# Connectors_U_B.net
KiCad netlist of a schematic drawn in Altium Designer
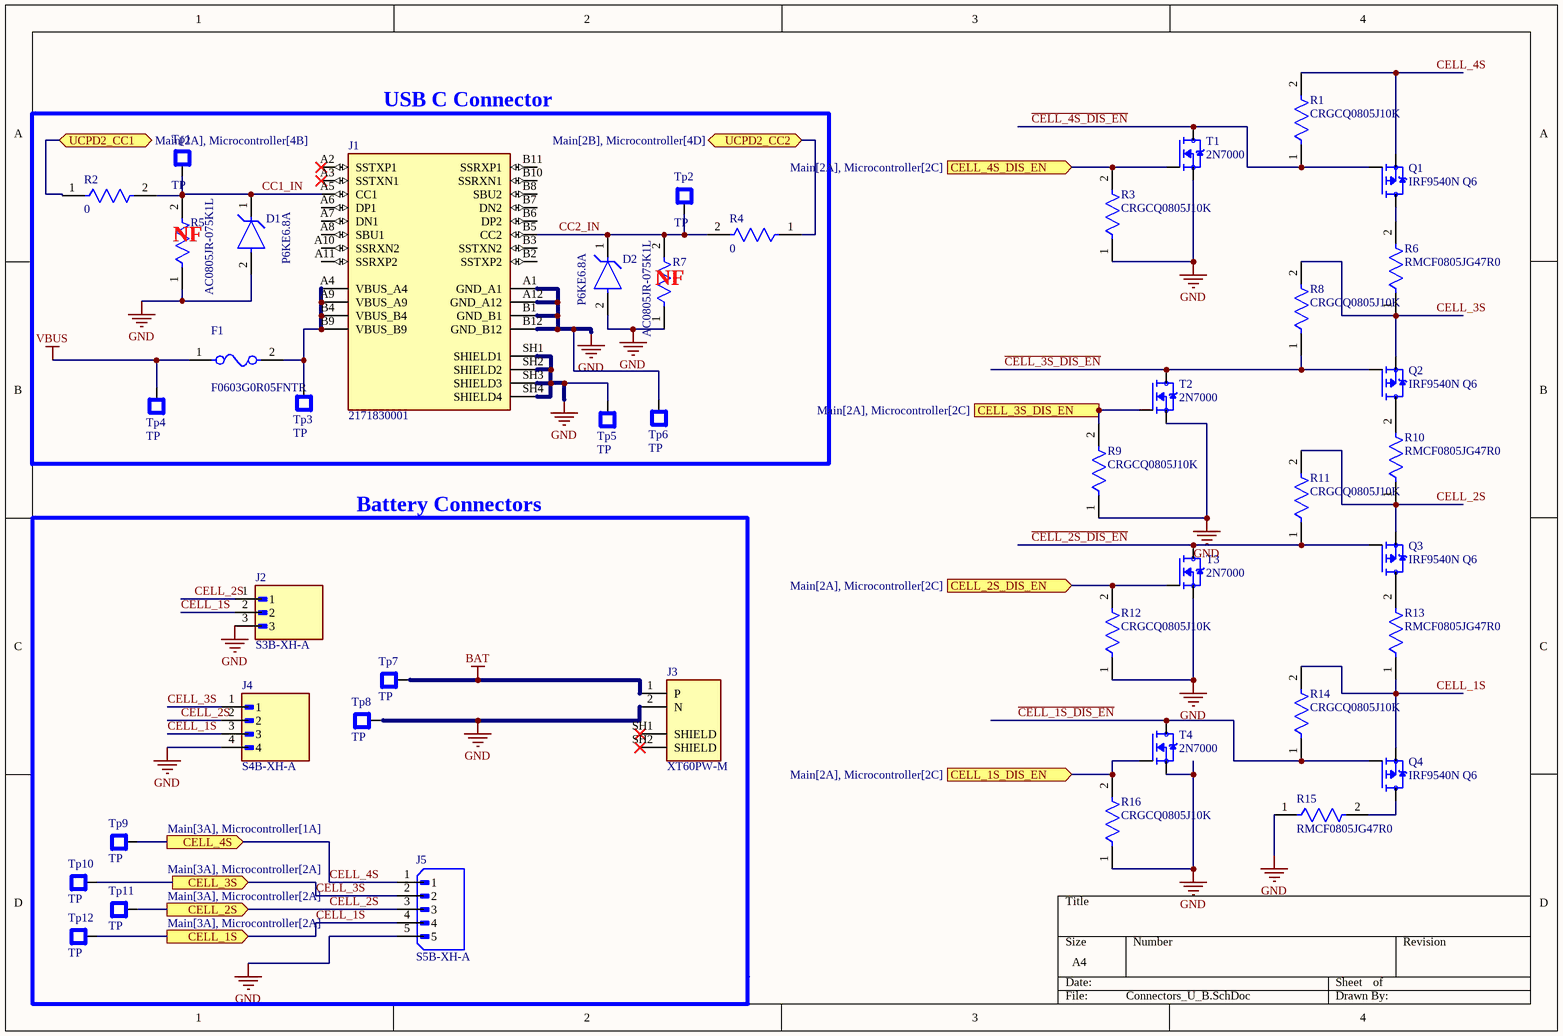
[diagram p0: Connectors_U_B.SchDoc]

(export (version "E")
  (design (tool "Eeschema 10.0.6"))
  (components
    (comp (ref "D1")
      (value "P6KE6.8A")
      (footprint "FP-P6KE-MFG")
      (description "TVS DIODE 5.8V 10.5V DO204AC")
      (fields
        (field (name "MANUFACTURER") "Littelfuse Inc")
        (field (name "OCTOPART") "https://octopart.com/p6ke6.8a-littelfuse-20808")
      )
      (libsource (lib "Altium Content Vault") (part "f813f71cba58e380607f5dd3caf9714"))
    )
    (comp (ref "D2")
      (value "P6KE6.8A")
      (footprint "FP-P6KE-MFG")
      (description "TVS DIODE 5.8V 10.5V DO204AC")
      (fields
        (field (name "MANUFACTURER") "Littelfuse Inc")
        (field (name "OCTOPART") "https://octopart.com/p6ke6.8a-littelfuse-20808")
      )
      (libsource (lib "Altium Content Vault") (part "f813f71cba58e380607f5dd3caf9714"))
    )
    (comp (ref "F1")
      (value "F0603G0R05FNTR")
      (footprint "FP-F0603G-MFG")
      (description "FUSE BOARD MOUNT 50MA 32VDC 0603")
      (fields
        (field (name "OCTOPART") "https://octopart.com/f0603g0r05fntr-avx-21046321")
        (field (name "MANUFACTURER") "AVX Corporation")
      )
      (libsource (lib "Altium Content Vault") (part "5bcf9b9f640e542cf0359d10258e979"))
    )
    (comp (ref "J1")
      (value "2171830001")
      (footprint "MOLEX_2171830001")
      (fields (field (name "MF") "{'manufacturer': u'Molex'}"))
      (libsource (lib "power_schi") (part "2171830001"))
    )
    (comp (ref "J2")
      (value "S3B-XH-A")
      (footprint "JST_S3B-XH-A")
      (libsource (lib "power_schi") (part "S3B-XH-A"))
    )
    (comp (ref "J3")
      (value "XT60PW-M")
      (footprint "AMASS_XT60PW-M")
      (description "Socket, DC supply, male, PIN: 2")
      (fields (field (name "MF") "AMASS"))
      (libsource (lib "power_schi") (part "XT60PW-M"))
    )
    (comp (ref "J4")
      (value "S4B-XH-A")
      (footprint "JST_S4B-XH-A")
      (libsource (lib "power_schi") (part "S4B-XH-A"))
    )
    (comp (ref "J5")
      (value "S5B-XH-A")
      (footprint "JST_S5B-XH-A")
      (description "Connector Header Through Hole, Right Angle 5 position 0.098 (2.50mm)")
      (fields (field (name "MF") "JST Sales"))
      (libsource (lib "power_schi") (part "S5B-XH-A"))
    )
    (comp (ref "Q1")
      (value "IRF9540N Q6")
      (footprint "TO254P1041X444X1930-3")
      (description "P-Channel 100 V 23A (Tc) 3.1W (Ta), 110W (Tc)")
      (fields (field (name "MF") "Infineon Technologies") (field (name "MP") "IRF9540N"))
      (libsource (lib "power_schi") (part "IRF9540N Q6"))
    )
    (comp (ref "Q2")
      (value "IRF9540N Q6")
      (footprint "TO254P1041X444X1930-3")
      (description "P-Channel 100 V 23A (Tc) 3.1W (Ta), 110W (Tc)")
      (fields (field (name "MF") "Infineon Technologies") (field (name "MP") "IRF9540N"))
      (libsource (lib "power_schi") (part "IRF9540N Q6"))
    )
    (comp (ref "Q3")
      (value "IRF9540N Q6")
      (footprint "TO254P1041X444X1930-3")
      (description "P-Channel 100 V 23A (Tc) 3.1W (Ta), 110W (Tc)")
      (fields (field (name "MF") "Infineon Technologies") (field (name "MP") "IRF9540N"))
      (libsource (lib "power_schi") (part "IRF9540N Q6"))
    )
    (comp (ref "Q4")
      (value "IRF9540N Q6")
      (footprint "TO254P1041X444X1930-3")
      (description "P-Channel 100 V 23A (Tc) 3.1W (Ta), 110W (Tc)")
      (fields (field (name "MF") "Infineon Technologies") (field (name "MP") "IRF9540N"))
      (libsource (lib "power_schi") (part "IRF9540N Q6"))
    )
    (comp (ref "R1")
      (value "CRGCQ0805J10K")
      (footprint "FP-CRGCQ0805-IPC_C")
      (description "CRGCQ 0805 10K 5%")
      (fields (field (name "MANUFACTURER") "TE Connectivity") (field (name "TOLERANCE") "0.05"))
      (libsource (lib "Altium Content Vault") (part "1029c3af85768c4190bb7ad29bc67b5"))
    )
    (comp (ref "R2")
      (value "0")
      (footprint "FP-HCJ0805-MFG")
      (description "RES 0 OHM JUMPER 1/2W 0805")
      (libsource (lib "Altium Content Vault") (part "1029c3af85768c4190bb7ad29bc67b5"))
    )
    (comp (ref "R3")
      (value "CRGCQ0805J10K")
      (footprint "FP-CRGCQ0805-IPC_C")
      (description "CRGCQ 0805 10K 5%")
      (fields (field (name "MANUFACTURER") "TE Connectivity") (field (name "TOLERANCE") "0.05"))
      (libsource (lib "Altium Content Vault") (part "1029c3af85768c4190bb7ad29bc67b5"))
    )
    (comp (ref "R4")
      (value "0")
      (footprint "FP-HCJ0805-MFG")
      (description "RES 0 OHM JUMPER 1/2W 0805")
      (libsource (lib "Altium Content Vault") (part "1029c3af85768c4190bb7ad29bc67b5"))
    )
    (comp (ref "R5")
      (value "AC0805JR-075K1L")
      (footprint "FP-AC0805-MFG")
      (description "RES SMD 5.1K OHM 5% 1/8W 0805")
      (fields
        (field (name "OCTOPART") "https://octopart.com/ac0805jr-075k1l-yageo-21711115")
        (field (name "MANUFACTURER") "Yageo")
      )
      (libsource (lib "Altium Content Vault") (part "1029c3af85768c4190bb7ad29bc67b5"))
    )
    (comp (ref "R6")
      (value "RMCF0805JG47R0")
      (footprint "FP-RMCF0805-MFG")
      (description "47Ω ±5% 0.125W 0805 Thick Film Chip Resistor AEC-Q200 compliant")
      (fields (field (name "TOLERANCE") "5%"))
      (libsource (lib "Altium Content Vault") (part "1029c3af85768c4190bb7ad29bc67b5"))
    )
    (comp (ref "R7")
      (value "AC0805JR-075K1L")
      (footprint "FP-AC0805-MFG")
      (description "RES SMD 5.1K OHM 5% 1/8W 0805")
      (fields
        (field (name "OCTOPART") "https://octopart.com/ac0805jr-075k1l-yageo-21711115")
        (field (name "MANUFACTURER") "Yageo")
      )
      (libsource (lib "Altium Content Vault") (part "1029c3af85768c4190bb7ad29bc67b5"))
    )
    (comp (ref "R8")
      (value "CRGCQ0805J10K")
      (footprint "FP-CRGCQ0805-IPC_C")
      (description "CRGCQ 0805 10K 5%")
      (fields (field (name "MANUFACTURER") "TE Connectivity") (field (name "TOLERANCE") "0.05"))
      (libsource (lib "Altium Content Vault") (part "1029c3af85768c4190bb7ad29bc67b5"))
    )
    (comp (ref "R9")
      (value "CRGCQ0805J10K")
      (footprint "FP-CRGCQ0805-IPC_C")
      (description "CRGCQ 0805 10K 5%")
      (fields (field (name "MANUFACTURER") "TE Connectivity") (field (name "TOLERANCE") "0.05"))
      (libsource (lib "Altium Content Vault") (part "1029c3af85768c4190bb7ad29bc67b5"))
    )
    (comp (ref "R10")
      (value "RMCF0805JG47R0")
      (footprint "FP-RMCF0805-MFG")
      (description "47Ω ±5% 0.125W 0805 Thick Film Chip Resistor AEC-Q200 compliant")
      (fields (field (name "TOLERANCE") "5%"))
      (libsource (lib "Altium Content Vault") (part "1029c3af85768c4190bb7ad29bc67b5"))
    )
    (comp (ref "R11")
      (value "CRGCQ0805J10K")
      (footprint "FP-CRGCQ0805-IPC_C")
      (description "CRGCQ 0805 10K 5%")
      (fields (field (name "MANUFACTURER") "TE Connectivity") (field (name "TOLERANCE") "0.05"))
      (libsource (lib "Altium Content Vault") (part "1029c3af85768c4190bb7ad29bc67b5"))
    )
    (comp (ref "R12")
      (value "CRGCQ0805J10K")
      (footprint "FP-CRGCQ0805-IPC_C")
      (description "CRGCQ 0805 10K 5%")
      (fields (field (name "MANUFACTURER") "TE Connectivity") (field (name "TOLERANCE") "0.05"))
      (libsource (lib "Altium Content Vault") (part "1029c3af85768c4190bb7ad29bc67b5"))
    )
    (comp (ref "R13")
      (value "RMCF0805JG47R0")
      (footprint "FP-RMCF0805-MFG")
      (description "47Ω ±5% 0.125W 0805 Thick Film Chip Resistor AEC-Q200 compliant")
      (fields (field (name "TOLERANCE") "5%"))
      (libsource (lib "Altium Content Vault") (part "1029c3af85768c4190bb7ad29bc67b5"))
    )
    (comp (ref "R14")
      (value "CRGCQ0805J10K")
      (footprint "FP-CRGCQ0805-IPC_C")
      (description "CRGCQ 0805 10K 5%")
      (fields (field (name "MANUFACTURER") "TE Connectivity") (field (name "TOLERANCE") "0.05"))
      (libsource (lib "Altium Content Vault") (part "1029c3af85768c4190bb7ad29bc67b5"))
    )
    (comp (ref "R15")
      (value "RMCF0805JG47R0")
      (footprint "FP-RMCF0805-MFG")
      (description "47Ω ±5% 0.125W 0805 Thick Film Chip Resistor AEC-Q200 compliant")
      (fields (field (name "TOLERANCE") "5%"))
      (libsource (lib "Altium Content Vault") (part "1029c3af85768c4190bb7ad29bc67b5"))
    )
    (comp (ref "R16")
      (value "CRGCQ0805J10K")
      (footprint "FP-CRGCQ0805-IPC_C")
      (description "CRGCQ 0805 10K 5%")
      (fields (field (name "MANUFACTURER") "TE Connectivity") (field (name "TOLERANCE") "0.05"))
      (libsource (lib "Altium Content Vault") (part "1029c3af85768c4190bb7ad29bc67b5"))
    )
    (comp (ref "T1")
      (value "2N7000")
      (footprint "TO92")
      (description "N-Channel 60 V 200mA (Ta) 400mW (Ta) Through Hole TO-92-3")
      (fields (field (name "MF") "onsemi"))
      (libsource (lib "power_schi") (part "2N7000"))
    )
    (comp (ref "T2")
      (value "2N7000")
      (footprint "TO92")
      (description "N-Channel 60 V 200mA (Ta) 400mW (Ta) Through Hole TO-92-3")
      (fields (field (name "MF") "onsemi"))
      (libsource (lib "power_schi") (part "2N7000"))
    )
    (comp (ref "T3")
      (value "2N7000")
      (footprint "TO92")
      (description "N-Channel 60 V 200mA (Ta) 400mW (Ta) Through Hole TO-92-3")
      (fields (field (name "MF") "onsemi"))
      (libsource (lib "power_schi") (part "2N7000"))
    )
    (comp (ref "T4")
      (value "2N7000")
      (footprint "TO92")
      (description "N-Channel 60 V 200mA (Ta) 400mW (Ta) Through Hole TO-92-3")
      (fields (field (name "MF") "onsemi"))
      (libsource (lib "power_schi") (part "2N7000"))
    )
    (comp (ref "Tp1") (value "TP") (footprint "Tp") (libsource (lib "power_schi") (part "TP")))
    (comp (ref "Tp2") (value "TP") (footprint "Tp") (libsource (lib "power_schi") (part "TP")))
    (comp (ref "Tp3") (value "TP") (footprint "Tp") (libsource (lib "power_schi") (part "TP")))
    (comp (ref "Tp4") (value "TP") (footprint "Tp") (libsource (lib "power_schi") (part "TP")))
    (comp (ref "Tp5") (value "TP") (footprint "Tp") (libsource (lib "power_schi") (part "TP")))
    (comp (ref "Tp6") (value "TP") (footprint "Tp") (libsource (lib "power_schi") (part "TP")))
    (comp (ref "Tp7") (value "TP") (footprint "Tp") (libsource (lib "power_schi") (part "TP")))
    (comp (ref "Tp8") (value "TP") (footprint "Tp") (libsource (lib "power_schi") (part "TP")))
    (comp (ref "Tp9") (value "TP") (footprint "Tp") (libsource (lib "power_schi") (part "TP")))
    (comp (ref "Tp10") (value "TP") (footprint "Tp") (libsource (lib "power_schi") (part "TP")))
    (comp (ref "Tp11") (value "TP") (footprint "Tp") (libsource (lib "power_schi") (part "TP")))
    (comp (ref "Tp12") (value "TP") (footprint "Tp") (libsource (lib "power_schi") (part "TP")))
  )
  (nets
    (net (code "1") (name "/CC1_IN") (class "Default")
      (node (ref "D1") (pin "1") (pinfunction "C_1") (pintype "passive"))
      (node (ref "J1") (pin "A5") (pinfunction "CC1_A5") (pintype "bidirectional"))
      (node (ref "R2") (pin "2") (pinfunction "2_2") (pintype "passive"))
      (node (ref "R5") (pin "2") (pinfunction "2_2") (pintype "passive"))
      (node (ref "Tp1") (pin "1") (pinfunction "1_1") (pintype "passive"))
    )
    (net (code "2") (name "/CC2_IN") (class "Default")
      (node (ref "D2") (pin "1") (pinfunction "C_1") (pintype "passive"))
      (node (ref "J1") (pin "B5") (pinfunction "CC2_B5") (pintype "bidirectional"))
      (node (ref "R4") (pin "2") (pinfunction "2_2") (pintype "passive"))
      (node (ref "R7") (pin "2") (pinfunction "2_2") (pintype "passive"))
      (node (ref "Tp2") (pin "1") (pinfunction "1_1") (pintype "passive"))
    )
    (net (code "3") (name "/CELL_1S") (class "Default")
      (node (ref "J2") (pin "2") (pinfunction "2_2") (pintype "passive"))
      (node (ref "J4") (pin "3") (pinfunction "3_3") (pintype "passive"))
      (node (ref "J5") (pin "4") (pinfunction "4_4") (pintype "passive"))
      (node (ref "Q4") (pin "3") (pinfunction "S_3") (pintype "passive"))
      (node (ref "R13") (pin "1") (pinfunction "1_1") (pintype "passive"))
      (node (ref "R14") (pin "2") (pinfunction "2_2") (pintype "passive"))
      (node (ref "Tp12") (pin "1") (pinfunction "1_1") (pintype "passive"))
    )
    (net (code "4") (name "/CELL_1S_DIS_EN") (class "Default")
      (node (ref "R16") (pin "2") (pinfunction "2_2") (pintype "passive"))
      (node (ref "T4") (pin "2") (pinfunction "G_2") (pintype "passive"))
    )
    (net (code "5") (name "/CELL_2S") (class "Default")
      (node (ref "J2") (pin "1") (pinfunction "1_1") (pintype "passive"))
      (node (ref "J4") (pin "2") (pinfunction "2_2") (pintype "passive"))
      (node (ref "J5") (pin "3") (pinfunction "3_3") (pintype "passive"))
      (node (ref "Q3") (pin "3") (pinfunction "S_3") (pintype "passive"))
      (node (ref "R10") (pin "1") (pinfunction "1_1") (pintype "passive"))
      (node (ref "R11") (pin "2") (pinfunction "2_2") (pintype "passive"))
      (node (ref "Tp11") (pin "1") (pinfunction "1_1") (pintype "passive"))
    )
    (net (code "6") (name "/CELL_2S_DIS_EN") (class "Default")
      (node (ref "R12") (pin "2") (pinfunction "2_2") (pintype "passive"))
      (node (ref "T3") (pin "2") (pinfunction "G_2") (pintype "passive"))
    )
    (net (code "7") (name "/CELL_3S") (class "Default")
      (node (ref "J4") (pin "1") (pinfunction "1_1") (pintype "passive"))
      (node (ref "J5") (pin "2") (pinfunction "2_2") (pintype "passive"))
      (node (ref "Q2") (pin "3") (pinfunction "S_3") (pintype "passive"))
      (node (ref "R6") (pin "1") (pinfunction "1_1") (pintype "passive"))
      (node (ref "R8") (pin "2") (pinfunction "2_2") (pintype "passive"))
      (node (ref "Tp10") (pin "1") (pinfunction "1_1") (pintype "passive"))
    )
    (net (code "8") (name "/CELL_3S_DIS_EN") (class "Default")
      (node (ref "R9") (pin "2") (pinfunction "2_2") (pintype "passive"))
      (node (ref "T2") (pin "2") (pinfunction "G_2") (pintype "passive"))
    )
    (net (code "9") (name "/CELL_4S") (class "Default")
      (node (ref "J5") (pin "1") (pinfunction "1_1") (pintype "passive"))
      (node (ref "Q1") (pin "3") (pinfunction "S_3") (pintype "passive"))
      (node (ref "R1") (pin "2") (pinfunction "2_2") (pintype "passive"))
      (node (ref "Tp9") (pin "1") (pinfunction "1_1") (pintype "passive"))
    )
    (net (code "10") (name "/CELL_4S_DIS_EN") (class "Default")
      (node (ref "R3") (pin "2") (pinfunction "2_2") (pintype "passive"))
      (node (ref "T1") (pin "2") (pinfunction "G_2") (pintype "passive"))
    )
    (net (code "11") (name "/UCPD2_CC1") (class "Default")
      (node (ref "R2") (pin "1") (pinfunction "1_1") (pintype "passive"))
    )
    (net (code "12") (name "/UCPD2_CC2") (class "Default")
      (node (ref "R4") (pin "1") (pinfunction "1_1") (pintype "passive"))
    )
    (net (code "13") (name "/~{CELL_1S_DIS_EN}") (class "Default")
      (node (ref "Q4") (pin "1") (pinfunction "G_1") (pintype "passive"))
      (node (ref "R14") (pin "1") (pinfunction "1_1") (pintype "passive"))
      (node (ref "T4") (pin "3") (pinfunction "D_3") (pintype "passive"))
    )
    (net (code "14") (name "/~{CELL_2S_DIS_EN}") (class "Default")
      (node (ref "Q3") (pin "1") (pinfunction "G_1") (pintype "passive"))
      (node (ref "R11") (pin "1") (pinfunction "1_1") (pintype "passive"))
      (node (ref "T3") (pin "3") (pinfunction "D_3") (pintype "passive"))
    )
    (net (code "15") (name "/~{CELL_3S_DIS_EN}") (class "Default")
      (node (ref "Q2") (pin "1") (pinfunction "G_1") (pintype "passive"))
      (node (ref "R8") (pin "1") (pinfunction "1_1") (pintype "passive"))
      (node (ref "T2") (pin "3") (pinfunction "D_3") (pintype "passive"))
    )
    (net (code "16") (name "/~{CELL_4S_DIS_EN}") (class "Default")
      (node (ref "Q1") (pin "1") (pinfunction "G_1") (pintype "passive"))
      (node (ref "R1") (pin "1") (pinfunction "1_1") (pintype "passive"))
      (node (ref "T1") (pin "3") (pinfunction "D_3") (pintype "passive"))
    )
    (net (code "17") (name "BAT") (class "Default")
      (node (ref "J3") (pin "1") (pinfunction "P_1") (pintype "passive"))
      (node (ref "Tp7") (pin "1") (pinfunction "1_1") (pintype "passive"))
    )
    (net (code "18") (name "GND") (class "Default")
      (node (ref "D1") (pin "2") (pinfunction "A_2") (pintype "passive"))
      (node (ref "D2") (pin "2") (pinfunction "A_2") (pintype "passive"))
      (node (ref "J1") (pin "A1") (pinfunction "GND_A1_A1") (pintype "power_in"))
      (node (ref "J1") (pin "A12") (pinfunction "GND_A12_A12") (pintype "power_in"))
      (node (ref "J1") (pin "B1") (pinfunction "GND_B1_B1") (pintype "power_in"))
      (node (ref "J1") (pin "B12") (pinfunction "GND_B12_B12") (pintype "power_in"))
      (node (ref "J1") (pin "SH1") (pinfunction "SHIELD1_SH1") (pintype "passive"))
      (node (ref "J1") (pin "SH2") (pinfunction "SHIELD2_SH2") (pintype "passive"))
      (node (ref "J1") (pin "SH3") (pinfunction "SHIELD3_SH3") (pintype "passive"))
      (node (ref "J1") (pin "SH4") (pinfunction "SHIELD4_SH4") (pintype "passive"))
      (node (ref "J2") (pin "3") (pinfunction "3_3") (pintype "passive"))
      (node (ref "J3") (pin "2") (pinfunction "N_2") (pintype "passive"))
      (node (ref "J4") (pin "4") (pinfunction "4_4") (pintype "passive"))
      (node (ref "J5") (pin "5") (pinfunction "5_5") (pintype "passive"))
      (node (ref "R12") (pin "1") (pinfunction "1_1") (pintype "passive"))
      (node (ref "R15") (pin "1") (pinfunction "1_1") (pintype "passive"))
      (node (ref "R16") (pin "1") (pinfunction "1_1") (pintype "passive"))
      (node (ref "R3") (pin "1") (pinfunction "1_1") (pintype "passive"))
      (node (ref "R5") (pin "1") (pinfunction "1_1") (pintype "passive"))
      (node (ref "R7") (pin "1") (pinfunction "1_1") (pintype "passive"))
      (node (ref "R9") (pin "1") (pinfunction "1_1") (pintype "passive"))
      (node (ref "T1") (pin "1") (pinfunction "S_1") (pintype "passive"))
      (node (ref "T2") (pin "1") (pinfunction "S_1") (pintype "passive"))
      (node (ref "T3") (pin "1") (pinfunction "S_1") (pintype "passive"))
      (node (ref "T4") (pin "1") (pinfunction "S_1") (pintype "passive"))
      (node (ref "Tp5") (pin "1") (pinfunction "1_1") (pintype "passive"))
      (node (ref "Tp6") (pin "1") (pinfunction "1_1") (pintype "passive"))
      (node (ref "Tp8") (pin "1") (pinfunction "1_1") (pintype "passive"))
    )
    (net (code "19") (name "Net-(J1-VBUS_A4)") (class "Default")
      (node (ref "F1") (pin "2") (pinfunction "2_2") (pintype "passive"))
      (node (ref "J1") (pin "A4") (pinfunction "VBUS_A4_A4") (pintype "power_in"))
      (node (ref "J1") (pin "A9") (pinfunction "VBUS_A9_A9") (pintype "power_in"))
      (node (ref "J1") (pin "B4") (pinfunction "VBUS_B4_B4") (pintype "power_in"))
      (node (ref "J1") (pin "B9") (pinfunction "VBUS_B9_B9") (pintype "power_in"))
      (node (ref "Tp3") (pin "1") (pinfunction "1_1") (pintype "passive"))
    )
    (net (code "20") (name "Net-(Q1-D)") (class "Default")
      (node (ref "Q1") (pin "2") (pinfunction "D_2") (pintype "passive"))
      (node (ref "R6") (pin "2") (pinfunction "2_2") (pintype "passive"))
    )
    (net (code "21") (name "Net-(Q2-D)") (class "Default")
      (node (ref "Q2") (pin "2") (pinfunction "D_2") (pintype "passive"))
      (node (ref "R10") (pin "2") (pinfunction "2_2") (pintype "passive"))
    )
    (net (code "22") (name "Net-(Q3-D)") (class "Default")
      (node (ref "Q3") (pin "2") (pinfunction "D_2") (pintype "passive"))
      (node (ref "R13") (pin "2") (pinfunction "2_2") (pintype "passive"))
    )
    (net (code "23") (name "Net-(Q4-D)") (class "Default")
      (node (ref "Q4") (pin "2") (pinfunction "D_2") (pintype "passive"))
      (node (ref "R15") (pin "2") (pinfunction "2_2") (pintype "passive"))
    )
    (net (code "24") (name "VBUS") (class "Default")
      (node (ref "F1") (pin "1") (pinfunction "1_1") (pintype "passive"))
      (node (ref "Tp4") (pin "1") (pinfunction "1_1") (pintype "passive"))
    )
    (net (code "25") (name "unconnected-(J1-DN1-PadA7)") (class "Default")
      (node (ref "J1") (pin "A7") (pinfunction "DN1_A7") (pintype "bidirectional"))
    )
    (net (code "26") (name "unconnected-(J1-DN2-PadB7)") (class "Default")
      (node (ref "J1") (pin "B7") (pinfunction "DN2_B7") (pintype "bidirectional"))
    )
    (net (code "27") (name "unconnected-(J1-DP1-PadA6)") (class "Default")
      (node (ref "J1") (pin "A6") (pinfunction "DP1_A6") (pintype "bidirectional"))
    )
    (net (code "28") (name "unconnected-(J1-DP2-PadB6)") (class "Default")
      (node (ref "J1") (pin "B6") (pinfunction "DP2_B6") (pintype "bidirectional"))
    )
    (net (code "29") (name "unconnected-(J1-SBU1-PadA8)") (class "Default")
      (node (ref "J1") (pin "A8") (pinfunction "SBU1_A8") (pintype "bidirectional"))
    )
    (net (code "30") (name "unconnected-(J1-SBU2-PadB8)") (class "Default")
      (node (ref "J1") (pin "B8") (pinfunction "SBU2_B8") (pintype "bidirectional"))
    )
    (net (code "31") (name "unconnected-(J1-SSRXN1-PadB10)") (class "Default")
      (node (ref "J1") (pin "B10") (pinfunction "SSRXN1_B10") (pintype "bidirectional"))
    )
    (net (code "32") (name "unconnected-(J1-SSRXN2-PadA10)") (class "Default")
      (node (ref "J1") (pin "A10") (pinfunction "SSRXN2_A10") (pintype "bidirectional"))
    )
    (net (code "33") (name "unconnected-(J1-SSRXP1-PadB11)") (class "Default")
      (node (ref "J1") (pin "B11") (pinfunction "SSRXP1_B11") (pintype "bidirectional"))
    )
    (net (code "34") (name "unconnected-(J1-SSRXP2-PadA11)") (class "Default")
      (node (ref "J1") (pin "A11") (pinfunction "SSRXP2_A11") (pintype "bidirectional"))
    )
    (net (code "35") (name "unconnected-(J1-SSTXN1-PadA3)") (class "Default")
      (node (ref "J1") (pin "A3") (pinfunction "SSTXN1_A3") (pintype "bidirectional+no_connect"))
    )
    (net (code "36") (name "unconnected-(J1-SSTXN2-PadB3)") (class "Default")
      (node (ref "J1") (pin "B3") (pinfunction "SSTXN2_B3") (pintype "bidirectional"))
    )
    (net (code "37") (name "unconnected-(J1-SSTXP1-PadA2)") (class "Default")
      (node (ref "J1") (pin "A2") (pinfunction "SSTXP1_A2") (pintype "bidirectional+no_connect"))
    )
    (net (code "38") (name "unconnected-(J1-SSTXP2-PadB2)") (class "Default")
      (node (ref "J1") (pin "B2") (pinfunction "SSTXP2_B2") (pintype "bidirectional"))
    )
    (net (code "39") (name "unconnected-(J3-SHIELD-PadSH1)") (class "Default")
      (node (ref "J3") (pin "SH1") (pinfunction "SHIELD_SH1") (pintype "passive+no_connect"))
    )
    (net (code "40") (name "unconnected-(J3-SHIELD-PadSH2)") (class "Default")
      (node (ref "J3") (pin "SH2") (pinfunction "SHIELD_SH2") (pintype "passive+no_connect"))
    )
  )
)
